# Triggy.net
KiCad netlist of a schematic drawn in EAGLE
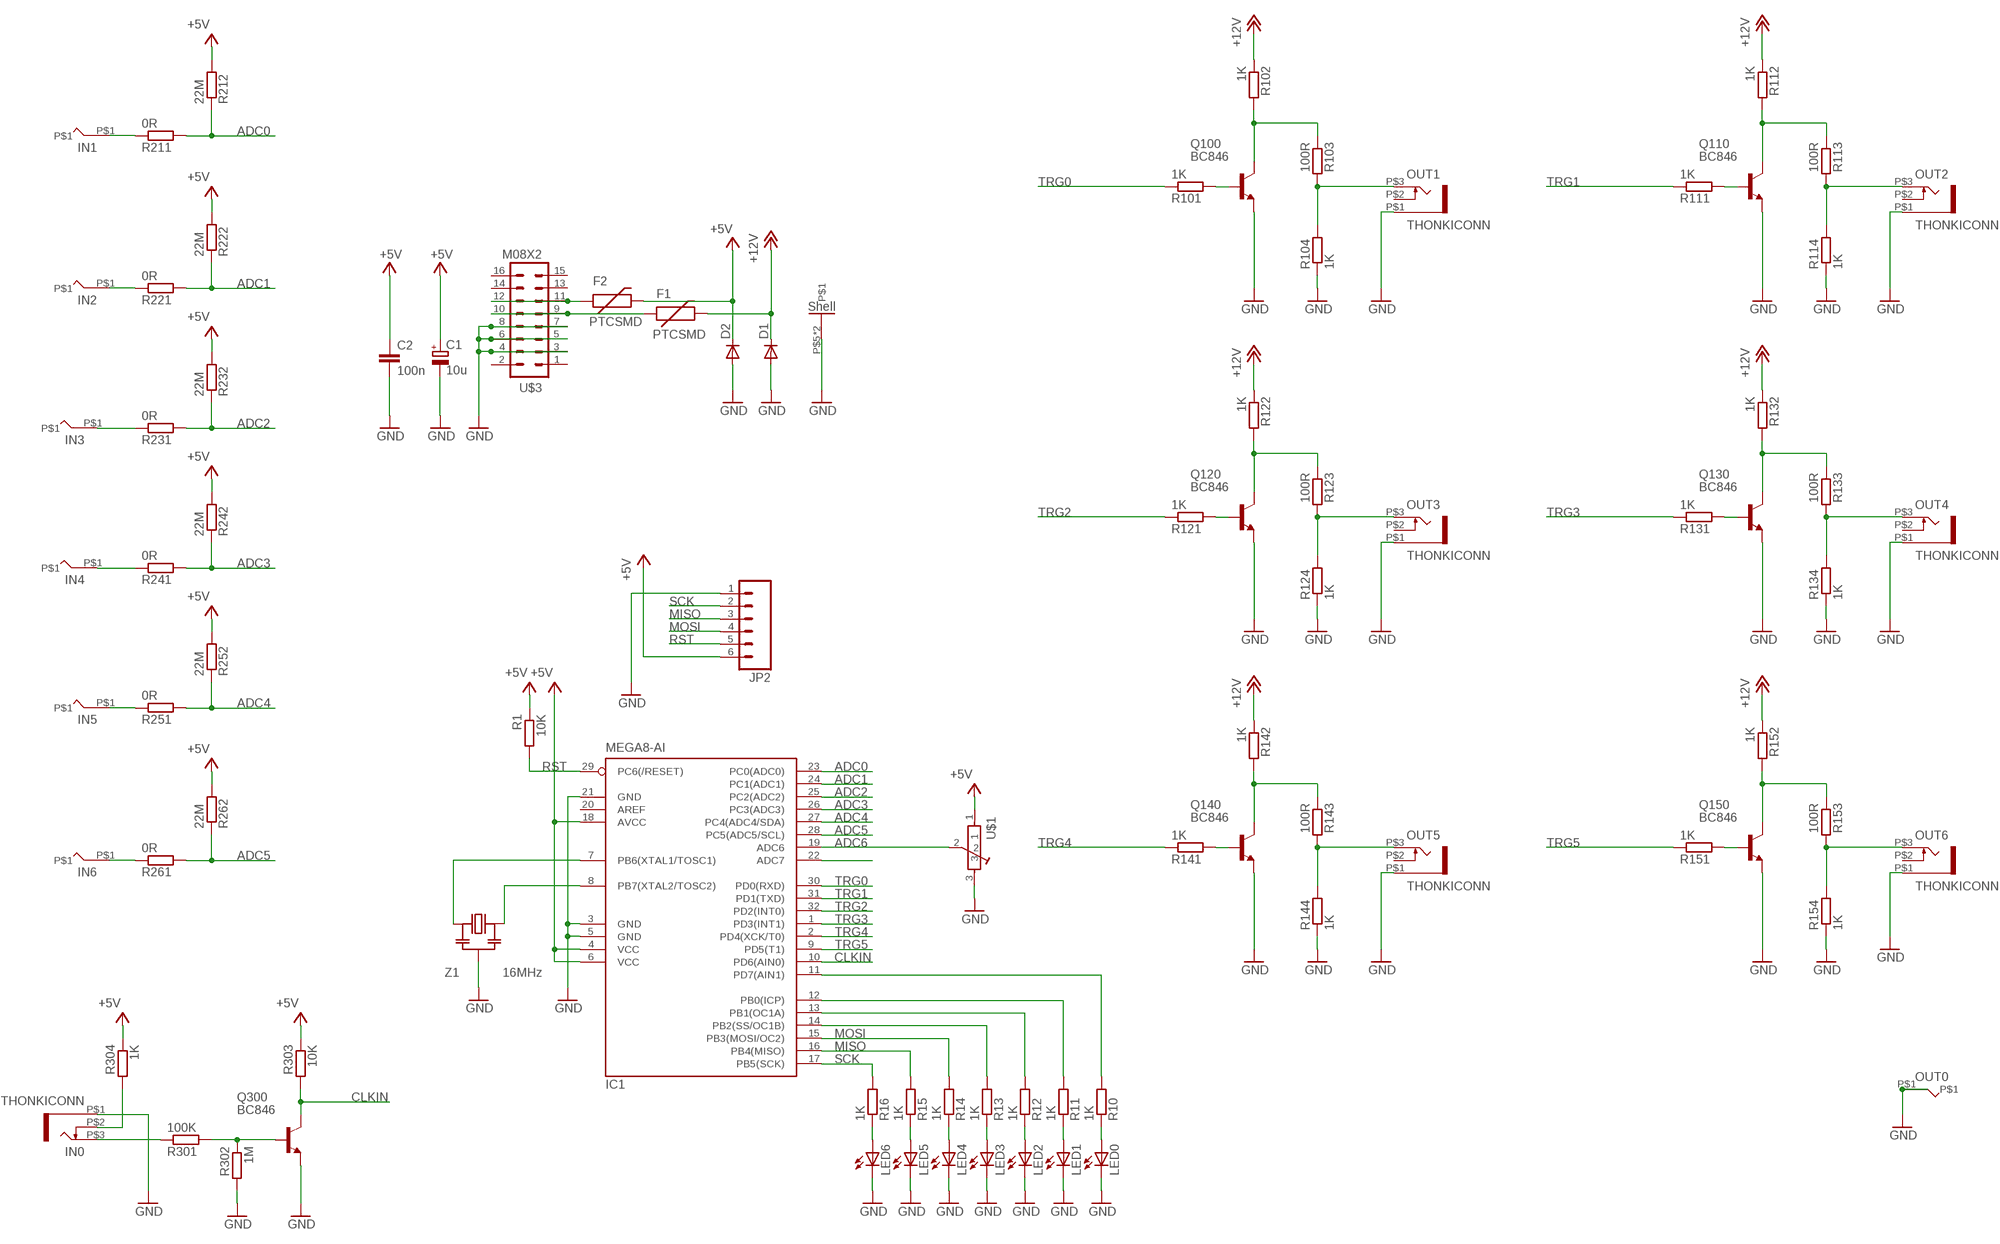
[diagram p0: schematic, sheet 1]

(export (version "E")
  (design (tool "Eeschema 10.0.6"))
  (components
    (comp (ref "C1")
      (value "10u")
      (footprint "eagle-import:E2,5-6")
      (libsource (lib "eagle-import") (part "CPOL-EUE2.5-6"))
    )
    (comp (ref "C2")
      (value "100n")
      (footprint "eagle-import:C0603")
      (libsource (lib "eagle-import") (part "C-EUC0603"))
    )
    (comp (ref "D1")
      (value "DIODESMA")
      (footprint "eagle-import:SMA-DIODE")
      (libsource (lib "eagle-import") (part "DIODESMA"))
    )
    (comp (ref "D2")
      (value "DIODESMA")
      (footprint "eagle-import:SMA-DIODE")
      (libsource (lib "eagle-import") (part "DIODESMA"))
    )
    (comp (ref "F1")
      (value "PTCSMD")
      (footprint "eagle-import:PTC-1206")
      (libsource (lib "eagle-import") (part "PTCSMD"))
    )
    (comp (ref "F2")
      (value "PTCSMD")
      (footprint "eagle-import:PTC-1206")
      (libsource (lib "eagle-import") (part "PTCSMD"))
    )
    (comp (ref "IC1")
      (value "MEGA8-AI")
      (footprint "eagle-import:TQFP32-08")
      (fields (field (name "MPN") "ATMEGA8-16AU"))
      (libsource (lib "eagle-import") (part "MEGA8-AI"))
    )
    (comp (ref "IN0")
      (value "THONKICONN")
      (footprint "eagle-import:THONKICONN")
      (libsource (lib "eagle-import") (part "THONKICONN"))
    )
    (comp (ref "IN1")
      (value "BANANAJACK")
      (footprint "eagle-import:BANANAJACK")
      (libsource (lib "eagle-import") (part "BANANAJACK"))
    )
    (comp (ref "IN2")
      (value "BANANAJACK")
      (footprint "eagle-import:BANANAJACK")
      (libsource (lib "eagle-import") (part "BANANAJACK"))
    )
    (comp (ref "IN3")
      (value "BANANAJACK")
      (footprint "eagle-import:BANANAJACK")
      (libsource (lib "eagle-import") (part "BANANAJACK"))
    )
    (comp (ref "IN4")
      (value "BANANAJACK")
      (footprint "eagle-import:BANANAJACK")
      (libsource (lib "eagle-import") (part "BANANAJACK"))
    )
    (comp (ref "IN5")
      (value "BANANAJACK")
      (footprint "eagle-import:BANANAJACK")
      (libsource (lib "eagle-import") (part "BANANAJACK"))
    )
    (comp (ref "IN6")
      (value "BANANAJACK")
      (footprint "eagle-import:BANANAJACK")
      (libsource (lib "eagle-import") (part "BANANAJACK"))
    )
    (comp (ref "JP2")
      (value "M06SIP")
      (footprint "eagle-import:1X06")
      (libsource (lib "eagle-import") (part "M06SIP"))
    )
    (comp (ref "LED0")
      (value "LED3MM")
      (footprint "eagle-import:LED3MM")
      (libsource (lib "eagle-import") (part "LED3MM"))
    )
    (comp (ref "LED1")
      (value "LED3MM")
      (footprint "eagle-import:LED3MM")
      (libsource (lib "eagle-import") (part "LED3MM"))
    )
    (comp (ref "LED2")
      (value "LED3MM")
      (footprint "eagle-import:LED3MM")
      (libsource (lib "eagle-import") (part "LED3MM"))
    )
    (comp (ref "LED3")
      (value "LED3MM")
      (footprint "eagle-import:LED3MM")
      (libsource (lib "eagle-import") (part "LED3MM"))
    )
    (comp (ref "LED4")
      (value "LED3MM")
      (footprint "eagle-import:LED3MM")
      (libsource (lib "eagle-import") (part "LED3MM"))
    )
    (comp (ref "LED5")
      (value "LED3MM")
      (footprint "eagle-import:LED3MM")
      (libsource (lib "eagle-import") (part "LED3MM"))
    )
    (comp (ref "LED6")
      (value "LED3MM")
      (footprint "eagle-import:LED3MM")
      (libsource (lib "eagle-import") (part "LED3MM"))
    )
    (comp (ref "OUT0")
      (value "BANANAJACK")
      (footprint "eagle-import:BANANAJACK")
      (libsource (lib "eagle-import") (part "BANANAJACK"))
    )
    (comp (ref "OUT1")
      (value "THONKICONN")
      (footprint "eagle-import:THONKICONN")
      (libsource (lib "eagle-import") (part "THONKICONN"))
    )
    (comp (ref "OUT2")
      (value "THONKICONN")
      (footprint "eagle-import:THONKICONN")
      (libsource (lib "eagle-import") (part "THONKICONN"))
    )
    (comp (ref "OUT3")
      (value "THONKICONN")
      (footprint "eagle-import:THONKICONN")
      (libsource (lib "eagle-import") (part "THONKICONN"))
    )
    (comp (ref "OUT4")
      (value "THONKICONN")
      (footprint "eagle-import:THONKICONN")
      (libsource (lib "eagle-import") (part "THONKICONN"))
    )
    (comp (ref "OUT5")
      (value "THONKICONN")
      (footprint "eagle-import:THONKICONN")
      (libsource (lib "eagle-import") (part "THONKICONN"))
    )
    (comp (ref "OUT6")
      (value "THONKICONN")
      (footprint "eagle-import:THONKICONN")
      (libsource (lib "eagle-import") (part "THONKICONN"))
    )
    (comp (ref "Q100")
      (value "BC846")
      (footprint "eagle-import:SOT23")
      (libsource (lib "eagle-import") (part "BC846"))
    )
    (comp (ref "Q110")
      (value "BC846")
      (footprint "eagle-import:SOT23")
      (libsource (lib "eagle-import") (part "BC846"))
    )
    (comp (ref "Q120")
      (value "BC846")
      (footprint "eagle-import:SOT23")
      (libsource (lib "eagle-import") (part "BC846"))
    )
    (comp (ref "Q130")
      (value "BC846")
      (footprint "eagle-import:SOT23")
      (libsource (lib "eagle-import") (part "BC846"))
    )
    (comp (ref "Q140")
      (value "BC846")
      (footprint "eagle-import:SOT23")
      (libsource (lib "eagle-import") (part "BC846"))
    )
    (comp (ref "Q150")
      (value "BC846")
      (footprint "eagle-import:SOT23")
      (libsource (lib "eagle-import") (part "BC846"))
    )
    (comp (ref "Q300")
      (value "BC846")
      (footprint "eagle-import:SOT23")
      (libsource (lib "eagle-import") (part "BC846"))
    )
    (comp (ref "R1")
      (value "10K")
      (footprint "eagle-import:0603")
      (libsource (lib "eagle-import") (part "R-EU_0603"))
    )
    (comp (ref "R10")
      (value "1K")
      (footprint "eagle-import:0603")
      (libsource (lib "eagle-import") (part "R-EU_0603"))
    )
    (comp (ref "R11")
      (value "1K")
      (footprint "eagle-import:0603")
      (libsource (lib "eagle-import") (part "R-EU_0603"))
    )
    (comp (ref "R12")
      (value "1K")
      (footprint "eagle-import:0603")
      (libsource (lib "eagle-import") (part "R-EU_0603"))
    )
    (comp (ref "R13")
      (value "1K")
      (footprint "eagle-import:0603")
      (libsource (lib "eagle-import") (part "R-EU_0603"))
    )
    (comp (ref "R14")
      (value "1K")
      (footprint "eagle-import:0603")
      (libsource (lib "eagle-import") (part "R-EU_0603"))
    )
    (comp (ref "R15")
      (value "1K")
      (footprint "eagle-import:0603")
      (libsource (lib "eagle-import") (part "R-EU_0603"))
    )
    (comp (ref "R16")
      (value "1K")
      (footprint "eagle-import:0603")
      (libsource (lib "eagle-import") (part "R-EU_0603"))
    )
    (comp (ref "R101")
      (value "1K")
      (footprint "eagle-import:0603")
      (libsource (lib "eagle-import") (part "R-EU_0603"))
    )
    (comp (ref "R102")
      (value "1K")
      (footprint "eagle-import:0603")
      (libsource (lib "eagle-import") (part "R-EU_0603"))
    )
    (comp (ref "R103")
      (value "100R")
      (footprint "eagle-import:0603")
      (libsource (lib "eagle-import") (part "R-EU_0603"))
    )
    (comp (ref "R104")
      (value "1K")
      (footprint "eagle-import:0603")
      (libsource (lib "eagle-import") (part "R-EU_0603"))
    )
    (comp (ref "R111")
      (value "1K")
      (footprint "eagle-import:0603")
      (libsource (lib "eagle-import") (part "R-EU_0603"))
    )
    (comp (ref "R112")
      (value "1K")
      (footprint "eagle-import:0603")
      (libsource (lib "eagle-import") (part "R-EU_0603"))
    )
    (comp (ref "R113")
      (value "100R")
      (footprint "eagle-import:0603")
      (libsource (lib "eagle-import") (part "R-EU_0603"))
    )
    (comp (ref "R114")
      (value "1K")
      (footprint "eagle-import:0603")
      (libsource (lib "eagle-import") (part "R-EU_0603"))
    )
    (comp (ref "R121")
      (value "1K")
      (footprint "eagle-import:0603")
      (libsource (lib "eagle-import") (part "R-EU_0603"))
    )
    (comp (ref "R122")
      (value "1K")
      (footprint "eagle-import:0603")
      (libsource (lib "eagle-import") (part "R-EU_0603"))
    )
    (comp (ref "R123")
      (value "100R")
      (footprint "eagle-import:0603")
      (libsource (lib "eagle-import") (part "R-EU_0603"))
    )
    (comp (ref "R124")
      (value "1K")
      (footprint "eagle-import:0603")
      (libsource (lib "eagle-import") (part "R-EU_0603"))
    )
    (comp (ref "R131")
      (value "1K")
      (footprint "eagle-import:0603")
      (libsource (lib "eagle-import") (part "R-EU_0603"))
    )
    (comp (ref "R132")
      (value "1K")
      (footprint "eagle-import:0603")
      (libsource (lib "eagle-import") (part "R-EU_0603"))
    )
    (comp (ref "R133")
      (value "100R")
      (footprint "eagle-import:0603")
      (libsource (lib "eagle-import") (part "R-EU_0603"))
    )
    (comp (ref "R134")
      (value "1K")
      (footprint "eagle-import:0603")
      (libsource (lib "eagle-import") (part "R-EU_0603"))
    )
    (comp (ref "R141")
      (value "1K")
      (footprint "eagle-import:0603")
      (libsource (lib "eagle-import") (part "R-EU_0603"))
    )
    (comp (ref "R142")
      (value "1K")
      (footprint "eagle-import:0603")
      (libsource (lib "eagle-import") (part "R-EU_0603"))
    )
    (comp (ref "R143")
      (value "100R")
      (footprint "eagle-import:0603")
      (libsource (lib "eagle-import") (part "R-EU_0603"))
    )
    (comp (ref "R144")
      (value "1K")
      (footprint "eagle-import:0603")
      (libsource (lib "eagle-import") (part "R-EU_0603"))
    )
    (comp (ref "R151")
      (value "1K")
      (footprint "eagle-import:0603")
      (libsource (lib "eagle-import") (part "R-EU_0603"))
    )
    (comp (ref "R152")
      (value "1K")
      (footprint "eagle-import:0603")
      (libsource (lib "eagle-import") (part "R-EU_0603"))
    )
    (comp (ref "R153")
      (value "100R")
      (footprint "eagle-import:0603")
      (libsource (lib "eagle-import") (part "R-EU_0603"))
    )
    (comp (ref "R154")
      (value "1K")
      (footprint "eagle-import:0603")
      (libsource (lib "eagle-import") (part "R-EU_0603"))
    )
    (comp (ref "R211")
      (value "0R")
      (footprint "eagle-import:0603")
      (libsource (lib "eagle-import") (part "R-EU_0603"))
    )
    (comp (ref "R212")
      (value "22M")
      (footprint "eagle-import:0603")
      (libsource (lib "eagle-import") (part "R-EU_0603"))
    )
    (comp (ref "R221")
      (value "0R")
      (footprint "eagle-import:0603")
      (libsource (lib "eagle-import") (part "R-EU_0603"))
    )
    (comp (ref "R222")
      (value "22M")
      (footprint "eagle-import:0603")
      (libsource (lib "eagle-import") (part "R-EU_0603"))
    )
    (comp (ref "R231")
      (value "0R")
      (footprint "eagle-import:0603")
      (libsource (lib "eagle-import") (part "R-EU_0603"))
    )
    (comp (ref "R232")
      (value "22M")
      (footprint "eagle-import:0603")
      (libsource (lib "eagle-import") (part "R-EU_0603"))
    )
    (comp (ref "R241")
      (value "0R")
      (footprint "eagle-import:0603")
      (libsource (lib "eagle-import") (part "R-EU_0603"))
    )
    (comp (ref "R242")
      (value "22M")
      (footprint "eagle-import:0603")
      (libsource (lib "eagle-import") (part "R-EU_0603"))
    )
    (comp (ref "R251")
      (value "0R")
      (footprint "eagle-import:0603")
      (libsource (lib "eagle-import") (part "R-EU_0603"))
    )
    (comp (ref "R252")
      (value "22M")
      (footprint "eagle-import:0603")
      (libsource (lib "eagle-import") (part "R-EU_0603"))
    )
    (comp (ref "R261")
      (value "0R")
      (footprint "eagle-import:0603")
      (libsource (lib "eagle-import") (part "R-EU_0603"))
    )
    (comp (ref "R262")
      (value "22M")
      (footprint "eagle-import:0603")
      (libsource (lib "eagle-import") (part "R-EU_0603"))
    )
    (comp (ref "R301")
      (value "100K")
      (footprint "eagle-import:0603")
      (libsource (lib "eagle-import") (part "R-EU_0603"))
    )
    (comp (ref "R302")
      (value "1M")
      (footprint "eagle-import:0603")
      (libsource (lib "eagle-import") (part "R-EU_0603"))
    )
    (comp (ref "R303")
      (value "10K")
      (footprint "eagle-import:0603")
      (libsource (lib "eagle-import") (part "R-EU_0603"))
    )
    (comp (ref "R304")
      (value "1K")
      (footprint "eagle-import:0603")
      (libsource (lib "eagle-import") (part "R-EU_0603"))
    )
    (comp (ref "U$1")
      (value "POT-ALPS-RK09L1140")
      (footprint "eagle-import:POT-ALPS-RK09L1140")
      (libsource (lib "eagle-import") (part "POT-ALPS-RK09L1140"))
    )
    (comp (ref "U$3")
      (value "M08X2")
      (footprint "eagle-import:2X8")
      (libsource (lib "eagle-import") (part "M08X2"))
    )
    (comp (ref "Z1")
      (value "16MHz")
      (footprint "eagle-import:CSTCE_G_A")
      (libsource (lib "eagle-import") (part "CERAMIC_RESONATOR"))
    )
  )
  (nets
    (net (code "1") (name "+5V") (class "Default")
      (node (ref "C1") (pin "+") (pinfunction "+_+") (pintype "passive"))
      (node (ref "C2") (pin "1") (pinfunction "1_1") (pintype "passive"))
      (node (ref "D2") (pin "C") (pinfunction "C_C") (pintype "passive"))
      (node (ref "F2") (pin "2") (pinfunction "2_2") (pintype "bidirectional"))
      (node (ref "IC1") (pin "18") (pinfunction "AVCC_18") (pintype "power_in"))
      (node (ref "IC1") (pin "4") (pinfunction "VCC_4") (pintype "power_in"))
      (node (ref "IC1") (pin "6") (pinfunction "VCC_6") (pintype "power_in"))
      (node (ref "JP2") (pin "6") (pinfunction "6_6") (pintype "passive"))
      (node (ref "R1") (pin "1") (pinfunction "1_1") (pintype "passive"))
      (node (ref "R212") (pin "2") (pinfunction "2_2") (pintype "passive"))
      (node (ref "R222") (pin "2") (pinfunction "2_2") (pintype "passive"))
      (node (ref "R232") (pin "2") (pinfunction "2_2") (pintype "passive"))
      (node (ref "R242") (pin "2") (pinfunction "2_2") (pintype "passive"))
      (node (ref "R252") (pin "2") (pinfunction "2_2") (pintype "passive"))
      (node (ref "R262") (pin "2") (pinfunction "2_2") (pintype "passive"))
      (node (ref "R303") (pin "1") (pinfunction "1_1") (pintype "passive"))
      (node (ref "R304") (pin "1") (pinfunction "1_1") (pintype "passive"))
      (node (ref "U$1") (pin "1") (pinfunction "1_1") (pintype "bidirectional"))
    )
    (net (code "2") (name "+12V") (class "Default")
      (node (ref "D1") (pin "C") (pinfunction "C_C") (pintype "passive"))
      (node (ref "F1") (pin "2") (pinfunction "2_2") (pintype "bidirectional"))
      (node (ref "R102") (pin "1") (pinfunction "1_1") (pintype "passive"))
      (node (ref "R112") (pin "1") (pinfunction "1_1") (pintype "passive"))
      (node (ref "R122") (pin "1") (pinfunction "1_1") (pintype "passive"))
      (node (ref "R132") (pin "1") (pinfunction "1_1") (pintype "passive"))
      (node (ref "R142") (pin "1") (pinfunction "1_1") (pintype "passive"))
      (node (ref "R152") (pin "1") (pinfunction "1_1") (pintype "passive"))
    )
    (net (code "3") (name "/ADC0") (class "Default")
      (node (ref "IC1") (pin "23") (pinfunction "PC0(ADC0)_23") (pintype "bidirectional"))
      (node (ref "R211") (pin "2") (pinfunction "2_2") (pintype "passive"))
      (node (ref "R212") (pin "1") (pinfunction "1_1") (pintype "passive"))
    )
    (net (code "4") (name "/ADC1") (class "Default")
      (node (ref "IC1") (pin "24") (pinfunction "PC1(ADC1)_24") (pintype "bidirectional"))
      (node (ref "R221") (pin "2") (pinfunction "2_2") (pintype "passive"))
      (node (ref "R222") (pin "1") (pinfunction "1_1") (pintype "passive"))
    )
    (net (code "5") (name "/ADC2") (class "Default")
      (node (ref "IC1") (pin "25") (pinfunction "PC2(ADC2)_25") (pintype "bidirectional"))
      (node (ref "R231") (pin "2") (pinfunction "2_2") (pintype "passive"))
      (node (ref "R232") (pin "1") (pinfunction "1_1") (pintype "passive"))
    )
    (net (code "6") (name "/ADC3") (class "Default")
      (node (ref "IC1") (pin "26") (pinfunction "PC3(ADC3)_26") (pintype "bidirectional"))
      (node (ref "R241") (pin "2") (pinfunction "2_2") (pintype "passive"))
      (node (ref "R242") (pin "1") (pinfunction "1_1") (pintype "passive"))
    )
    (net (code "7") (name "/ADC4") (class "Default")
      (node (ref "IC1") (pin "27") (pinfunction "PC4(ADC4/SDA)_27") (pintype "bidirectional"))
      (node (ref "R251") (pin "2") (pinfunction "2_2") (pintype "passive"))
      (node (ref "R252") (pin "1") (pinfunction "1_1") (pintype "passive"))
    )
    (net (code "8") (name "/ADC5") (class "Default")
      (node (ref "IC1") (pin "28") (pinfunction "PC5(ADC5/SCL)_28") (pintype "bidirectional"))
      (node (ref "R261") (pin "2") (pinfunction "2_2") (pintype "passive"))
      (node (ref "R262") (pin "1") (pinfunction "1_1") (pintype "passive"))
    )
    (net (code "9") (name "/ADC6") (class "Default")
      (node (ref "IC1") (pin "19") (pinfunction "ADC6_19") (pintype "bidirectional"))
      (node (ref "U$1") (pin "2") (pinfunction "2_2") (pintype "bidirectional"))
    )
    (net (code "10") (name "/CLKIN") (class "Default")
      (node (ref "IC1") (pin "10") (pinfunction "PD6(AIN0)_10") (pintype "bidirectional"))
      (node (ref "Q300") (pin "3") (pinfunction "C_3") (pintype "passive"))
      (node (ref "R303") (pin "2") (pinfunction "2_2") (pintype "passive"))
    )
    (net (code "11") (name "/MISO") (class "Default")
      (node (ref "IC1") (pin "16") (pinfunction "PB4(MISO)_16") (pintype "bidirectional"))
      (node (ref "JP2") (pin "3") (pinfunction "3_3") (pintype "passive"))
      (node (ref "R15") (pin "2") (pinfunction "2_2") (pintype "passive"))
    )
    (net (code "12") (name "/MOSI") (class "Default")
      (node (ref "IC1") (pin "15") (pinfunction "PB3(MOSI/OC2)_15") (pintype "bidirectional"))
      (node (ref "JP2") (pin "4") (pinfunction "4_4") (pintype "passive"))
      (node (ref "R14") (pin "2") (pinfunction "2_2") (pintype "passive"))
    )
    (net (code "13") (name "/RST") (class "Default")
      (node (ref "IC1") (pin "29") (pinfunction "PC6(/RESET)_29") (pintype "bidirectional"))
      (node (ref "JP2") (pin "5") (pinfunction "5_5") (pintype "passive"))
      (node (ref "R1") (pin "2") (pinfunction "2_2") (pintype "passive"))
    )
    (net (code "14") (name "/SCK") (class "Default")
      (node (ref "IC1") (pin "17") (pinfunction "PB5(SCK)_17") (pintype "bidirectional"))
      (node (ref "JP2") (pin "2") (pinfunction "2_2") (pintype "passive"))
      (node (ref "R16") (pin "2") (pinfunction "2_2") (pintype "passive"))
    )
    (net (code "15") (name "/TRG0") (class "Default")
      (node (ref "IC1") (pin "30") (pinfunction "PD0(RXD)_30") (pintype "bidirectional"))
      (node (ref "R101") (pin "1") (pinfunction "1_1") (pintype "passive"))
    )
    (net (code "16") (name "/TRG1") (class "Default")
      (node (ref "IC1") (pin "31") (pinfunction "PD1(TXD)_31") (pintype "bidirectional"))
      (node (ref "R111") (pin "1") (pinfunction "1_1") (pintype "passive"))
    )
    (net (code "17") (name "/TRG2") (class "Default")
      (node (ref "IC1") (pin "32") (pinfunction "PD2(INT0)_32") (pintype "bidirectional"))
      (node (ref "R121") (pin "1") (pinfunction "1_1") (pintype "passive"))
    )
    (net (code "18") (name "/TRG3") (class "Default")
      (node (ref "IC1") (pin "1") (pinfunction "PD3(INT1)_1") (pintype "bidirectional"))
      (node (ref "R131") (pin "1") (pinfunction "1_1") (pintype "passive"))
    )
    (net (code "19") (name "/TRG4") (class "Default")
      (node (ref "IC1") (pin "2") (pinfunction "PD4(XCK/T0)_2") (pintype "bidirectional"))
      (node (ref "R141") (pin "1") (pinfunction "1_1") (pintype "passive"))
    )
    (net (code "20") (name "/TRG5") (class "Default")
      (node (ref "IC1") (pin "9") (pinfunction "PD5(T1)_9") (pintype "bidirectional"))
      (node (ref "R151") (pin "1") (pinfunction "1_1") (pintype "passive"))
    )
    (net (code "21") (name "GND") (class "Default")
      (node (ref "C1") (pin "-") (pinfunction "-_-") (pintype "passive"))
      (node (ref "C2") (pin "2") (pinfunction "2_2") (pintype "passive"))
      (node (ref "D1") (pin "A") (pinfunction "A_A") (pintype "passive"))
      (node (ref "D2") (pin "A") (pinfunction "A_A") (pintype "passive"))
      (node (ref "IC1") (pin "21") (pinfunction "GND_21") (pintype "power_in"))
      (node (ref "IC1") (pin "3") (pinfunction "GND_3") (pintype "power_in"))
      (node (ref "IC1") (pin "5") (pinfunction "GND_5") (pintype "power_in"))
      (node (ref "IN0") (pin "P$1") (pinfunction "5_P$1") (pintype "passive"))
      (node (ref "JP2") (pin "1") (pinfunction "1_1") (pintype "passive"))
      (node (ref "LED0") (pin "K") (pinfunction "C_K") (pintype "passive"))
      (node (ref "LED1") (pin "K") (pinfunction "C_K") (pintype "passive"))
      (node (ref "LED2") (pin "K") (pinfunction "C_K") (pintype "passive"))
      (node (ref "LED3") (pin "K") (pinfunction "C_K") (pintype "passive"))
      (node (ref "LED4") (pin "K") (pinfunction "C_K") (pintype "passive"))
      (node (ref "LED5") (pin "K") (pinfunction "C_K") (pintype "passive"))
      (node (ref "LED6") (pin "K") (pinfunction "C_K") (pintype "passive"))
      (node (ref "OUT0") (pin "P$1") (pinfunction "P$1_P$1") (pintype "bidirectional"))
      (node (ref "OUT1") (pin "P$1") (pinfunction "5_P$1") (pintype "passive"))
      (node (ref "OUT2") (pin "P$1") (pinfunction "5_P$1") (pintype "passive"))
      (node (ref "OUT3") (pin "P$1") (pinfunction "5_P$1") (pintype "passive"))
      (node (ref "OUT4") (pin "P$1") (pinfunction "5_P$1") (pintype "passive"))
      (node (ref "OUT5") (pin "P$1") (pinfunction "5_P$1") (pintype "passive"))
      (node (ref "OUT6") (pin "P$1") (pinfunction "5_P$1") (pintype "passive"))
      (node (ref "Q100") (pin "2") (pinfunction "E_2") (pintype "passive"))
      (node (ref "Q110") (pin "2") (pinfunction "E_2") (pintype "passive"))
      (node (ref "Q120") (pin "2") (pinfunction "E_2") (pintype "passive"))
      (node (ref "Q130") (pin "2") (pinfunction "E_2") (pintype "passive"))
      (node (ref "Q140") (pin "2") (pinfunction "E_2") (pintype "passive"))
      (node (ref "Q150") (pin "2") (pinfunction "E_2") (pintype "passive"))
      (node (ref "Q300") (pin "2") (pinfunction "E_2") (pintype "passive"))
      (node (ref "R104") (pin "1") (pinfunction "1_1") (pintype "passive"))
      (node (ref "R114") (pin "1") (pinfunction "1_1") (pintype "passive"))
      (node (ref "R124") (pin "1") (pinfunction "1_1") (pintype "passive"))
      (node (ref "R134") (pin "1") (pinfunction "1_1") (pintype "passive"))
      (node (ref "R144") (pin "1") (pinfunction "1_1") (pintype "passive"))
      (node (ref "R154") (pin "1") (pinfunction "1_1") (pintype "passive"))
      (node (ref "R302") (pin "2") (pinfunction "2_2") (pintype "passive"))
      (node (ref "U$1") (pin "3") (pinfunction "3_3") (pintype "bidirectional"))
      (node (ref "U$1") (pin "P$5") (pinfunction "P$1_P$5") (pintype "bidirectional"))
      (node (ref "U$1") (pin "P$6") (pinfunction "P$1_P$6") (pintype "bidirectional"))
      (node (ref "U$3") (pin "3") (pinfunction "3_3") (pintype "passive"))
      (node (ref "U$3") (pin "4") (pinfunction "4_4") (pintype "passive"))
      (node (ref "U$3") (pin "5") (pinfunction "5_5") (pintype "passive"))
      (node (ref "U$3") (pin "6") (pinfunction "6_6") (pintype "passive"))
      (node (ref "U$3") (pin "7") (pinfunction "7_7") (pintype "passive"))
      (node (ref "U$3") (pin "8") (pinfunction "8_8") (pintype "passive"))
      (node (ref "Z1") (pin "P$2") (pinfunction "GND_P$2") (pintype "bidirectional"))
    )
    (net (code "22") (name "Net-(F1-Pad1)") (class "Default")
      (node (ref "F1") (pin "1") (pinfunction "1_1") (pintype "bidirectional"))
      (node (ref "U$3") (pin "10") (pinfunction "10_10") (pintype "passive"))
      (node (ref "U$3") (pin "9") (pinfunction "9_9") (pintype "passive"))
    )
    (net (code "23") (name "Net-(F2-Pad1)") (class "Default")
      (node (ref "F2") (pin "1") (pinfunction "1_1") (pintype "bidirectional"))
      (node (ref "U$3") (pin "11") (pinfunction "11_11") (pintype "passive"))
      (node (ref "U$3") (pin "12") (pinfunction "12_12") (pintype "passive"))
    )
    (net (code "24") (name "Net-(IC1-PB0(ICP))") (class "Default")
      (node (ref "IC1") (pin "12") (pinfunction "PB0(ICP)_12") (pintype "bidirectional"))
      (node (ref "R11") (pin "2") (pinfunction "2_2") (pintype "passive"))
    )
    (net (code "25") (name "Net-(IC1-PB1(OC1A))") (class "Default")
      (node (ref "IC1") (pin "13") (pinfunction "PB1(OC1A)_13") (pintype "bidirectional"))
      (node (ref "R12") (pin "2") (pinfunction "2_2") (pintype "passive"))
    )
    (net (code "26") (name "Net-(IC1-PB2(SS{slash}OC1B))") (class "Default")
      (node (ref "IC1") (pin "14") (pinfunction "PB2(SS/OC1B)_14") (pintype "bidirectional"))
      (node (ref "R13") (pin "2") (pinfunction "2_2") (pintype "passive"))
    )
    (net (code "27") (name "Net-(IC1-PB6(XTAL1{slash}TOSC1))") (class "Default")
      (node (ref "IC1") (pin "7") (pinfunction "PB6(XTAL1/TOSC1)_7") (pintype "bidirectional"))
      (node (ref "Z1") (pin "P$1") (pinfunction "IN_P$1") (pintype "bidirectional"))
    )
    (net (code "28") (name "Net-(IC1-PB7(XTAL2{slash}TOSC2))") (class "Default")
      (node (ref "IC1") (pin "8") (pinfunction "PB7(XTAL2/TOSC2)_8") (pintype "bidirectional"))
      (node (ref "Z1") (pin "P$3") (pinfunction "OUT_P$3") (pintype "bidirectional"))
    )
    (net (code "29") (name "Net-(IC1-PD7(AIN1))") (class "Default")
      (node (ref "IC1") (pin "11") (pinfunction "PD7(AIN1)_11") (pintype "bidirectional"))
      (node (ref "R10") (pin "2") (pinfunction "2_2") (pintype "passive"))
    )
    (net (code "30") (name "Net-(IN0-3)") (class "Default")
      (node (ref "IN0") (pin "P$3") (pinfunction "3_P$3") (pintype "passive"))
      (node (ref "R301") (pin "1") (pinfunction "1_1") (pintype "passive"))
    )
    (net (code "31") (name "Net-(IN0-4)") (class "Default")
      (node (ref "IN0") (pin "P$2") (pinfunction "4_P$2") (pintype "passive"))
      (node (ref "R304") (pin "2") (pinfunction "2_2") (pintype "passive"))
    )
    (net (code "32") (name "Net-(IN1-PadP$1)") (class "Default")
      (node (ref "IN1") (pin "P$1") (pinfunction "P$1_P$1") (pintype "bidirectional"))
      (node (ref "R211") (pin "1") (pinfunction "1_1") (pintype "passive"))
    )
    (net (code "33") (name "Net-(IN2-PadP$1)") (class "Default")
      (node (ref "IN2") (pin "P$1") (pinfunction "P$1_P$1") (pintype "bidirectional"))
      (node (ref "R221") (pin "1") (pinfunction "1_1") (pintype "passive"))
    )
    (net (code "34") (name "Net-(IN3-PadP$1)") (class "Default")
      (node (ref "IN3") (pin "P$1") (pinfunction "P$1_P$1") (pintype "bidirectional"))
      (node (ref "R231") (pin "1") (pinfunction "1_1") (pintype "passive"))
    )
    (net (code "35") (name "Net-(IN4-PadP$1)") (class "Default")
      (node (ref "IN4") (pin "P$1") (pinfunction "P$1_P$1") (pintype "bidirectional"))
      (node (ref "R241") (pin "1") (pinfunction "1_1") (pintype "passive"))
    )
    (net (code "36") (name "Net-(IN5-PadP$1)") (class "Default")
      (node (ref "IN5") (pin "P$1") (pinfunction "P$1_P$1") (pintype "bidirectional"))
      (node (ref "R251") (pin "1") (pinfunction "1_1") (pintype "passive"))
    )
    (net (code "37") (name "Net-(IN6-PadP$1)") (class "Default")
      (node (ref "IN6") (pin "P$1") (pinfunction "P$1_P$1") (pintype "bidirectional"))
      (node (ref "R261") (pin "1") (pinfunction "1_1") (pintype "passive"))
    )
    (net (code "38") (name "Net-(LED0-PadA)") (class "Default")
      (node (ref "LED0") (pin "A") (pinfunction "A_A") (pintype "passive"))
      (node (ref "R10") (pin "1") (pinfunction "1_1") (pintype "passive"))
    )
    (net (code "39") (name "Net-(LED1-PadA)") (class "Default")
      (node (ref "LED1") (pin "A") (pinfunction "A_A") (pintype "passive"))
      (node (ref "R11") (pin "1") (pinfunction "1_1") (pintype "passive"))
    )
    (net (code "40") (name "Net-(LED2-PadA)") (class "Default")
      (node (ref "LED2") (pin "A") (pinfunction "A_A") (pintype "passive"))
      (node (ref "R12") (pin "1") (pinfunction "1_1") (pintype "passive"))
    )
    (net (code "41") (name "Net-(LED3-PadA)") (class "Default")
      (node (ref "LED3") (pin "A") (pinfunction "A_A") (pintype "passive"))
      (node (ref "R13") (pin "1") (pinfunction "1_1") (pintype "passive"))
    )
    (net (code "42") (name "Net-(LED4-PadA)") (class "Default")
      (node (ref "LED4") (pin "A") (pinfunction "A_A") (pintype "passive"))
      (node (ref "R14") (pin "1") (pinfunction "1_1") (pintype "passive"))
    )
    (net (code "43") (name "Net-(LED5-PadA)") (class "Default")
      (node (ref "LED5") (pin "A") (pinfunction "A_A") (pintype "passive"))
      (node (ref "R15") (pin "1") (pinfunction "1_1") (pintype "passive"))
    )
    (net (code "44") (name "Net-(LED6-PadA)") (class "Default")
      (node (ref "LED6") (pin "A") (pinfunction "A_A") (pintype "passive"))
      (node (ref "R16") (pin "1") (pinfunction "1_1") (pintype "passive"))
    )
    (net (code "45") (name "Net-(OUT1-3)") (class "Default")
      (node (ref "OUT1") (pin "P$3") (pinfunction "3_P$3") (pintype "passive"))
      (node (ref "R103") (pin "2") (pinfunction "2_2") (pintype "passive"))
      (node (ref "R104") (pin "2") (pinfunction "2_2") (pintype "passive"))
    )
    (net (code "46") (name "Net-(OUT2-3)") (class "Default")
      (node (ref "OUT2") (pin "P$3") (pinfunction "3_P$3") (pintype "passive"))
      (node (ref "R113") (pin "2") (pinfunction "2_2") (pintype "passive"))
      (node (ref "R114") (pin "2") (pinfunction "2_2") (pintype "passive"))
    )
    (net (code "47") (name "Net-(OUT3-3)") (class "Default")
      (node (ref "OUT3") (pin "P$3") (pinfunction "3_P$3") (pintype "passive"))
      (node (ref "R123") (pin "2") (pinfunction "2_2") (pintype "passive"))
      (node (ref "R124") (pin "2") (pinfunction "2_2") (pintype "passive"))
    )
    (net (code "48") (name "Net-(OUT4-3)") (class "Default")
      (node (ref "OUT4") (pin "P$3") (pinfunction "3_P$3") (pintype "passive"))
      (node (ref "R133") (pin "2") (pinfunction "2_2") (pintype "passive"))
      (node (ref "R134") (pin "2") (pinfunction "2_2") (pintype "passive"))
    )
    (net (code "49") (name "Net-(OUT5-3)") (class "Default")
      (node (ref "OUT5") (pin "P$3") (pinfunction "3_P$3") (pintype "passive"))
      (node (ref "R143") (pin "2") (pinfunction "2_2") (pintype "passive"))
      (node (ref "R144") (pin "2") (pinfunction "2_2") (pintype "passive"))
    )
    (net (code "50") (name "Net-(OUT6-3)") (class "Default")
      (node (ref "OUT6") (pin "P$3") (pinfunction "3_P$3") (pintype "passive"))
      (node (ref "R153") (pin "2") (pinfunction "2_2") (pintype "passive"))
      (node (ref "R154") (pin "2") (pinfunction "2_2") (pintype "passive"))
    )
    (net (code "51") (name "Net-(Q100-B)") (class "Default")
      (node (ref "Q100") (pin "1") (pinfunction "B_1") (pintype "passive"))
      (node (ref "R101") (pin "2") (pinfunction "2_2") (pintype "passive"))
    )
    (net (code "52") (name "Net-(Q100-C)") (class "Default")
      (node (ref "Q100") (pin "3") (pinfunction "C_3") (pintype "passive"))
      (node (ref "R102") (pin "2") (pinfunction "2_2") (pintype "passive"))
      (node (ref "R103") (pin "1") (pinfunction "1_1") (pintype "passive"))
    )
    (net (code "53") (name "Net-(Q110-B)") (class "Default")
      (node (ref "Q110") (pin "1") (pinfunction "B_1") (pintype "passive"))
      (node (ref "R111") (pin "2") (pinfunction "2_2") (pintype "passive"))
    )
    (net (code "54") (name "Net-(Q110-C)") (class "Default")
      (node (ref "Q110") (pin "3") (pinfunction "C_3") (pintype "passive"))
      (node (ref "R112") (pin "2") (pinfunction "2_2") (pintype "passive"))
      (node (ref "R113") (pin "1") (pinfunction "1_1") (pintype "passive"))
    )
    (net (code "55") (name "Net-(Q120-B)") (class "Default")
      (node (ref "Q120") (pin "1") (pinfunction "B_1") (pintype "passive"))
      (node (ref "R121") (pin "2") (pinfunction "2_2") (pintype "passive"))
    )
    (net (code "56") (name "Net-(Q120-C)") (class "Default")
      (node (ref "Q120") (pin "3") (pinfunction "C_3") (pintype "passive"))
      (node (ref "R122") (pin "2") (pinfunction "2_2") (pintype "passive"))
      (node (ref "R123") (pin "1") (pinfunction "1_1") (pintype "passive"))
    )
    (net (code "57") (name "Net-(Q130-B)") (class "Default")
      (node (ref "Q130") (pin "1") (pinfunction "B_1") (pintype "passive"))
      (node (ref "R131") (pin "2") (pinfunction "2_2") (pintype "passive"))
    )
    (net (code "58") (name "Net-(Q130-C)") (class "Default")
      (node (ref "Q130") (pin "3") (pinfunction "C_3") (pintype "passive"))
      (node (ref "R132") (pin "2") (pinfunction "2_2") (pintype "passive"))
      (node (ref "R133") (pin "1") (pinfunction "1_1") (pintype "passive"))
    )
    (net (code "59") (name "Net-(Q140-B)") (class "Default")
      (node (ref "Q140") (pin "1") (pinfunction "B_1") (pintype "passive"))
      (node (ref "R141") (pin "2") (pinfunction "2_2") (pintype "passive"))
    )
    (net (code "60") (name "Net-(Q140-C)") (class "Default")
      (node (ref "Q140") (pin "3") (pinfunction "C_3") (pintype "passive"))
      (node (ref "R142") (pin "2") (pinfunction "2_2") (pintype "passive"))
      (node (ref "R143") (pin "1") (pinfunction "1_1") (pintype "passive"))
    )
    (net (code "61") (name "Net-(Q150-B)") (class "Default")
      (node (ref "Q150") (pin "1") (pinfunction "B_1") (pintype "passive"))
      (node (ref "R151") (pin "2") (pinfunction "2_2") (pintype "passive"))
    )
    (net (code "62") (name "Net-(Q150-C)") (class "Default")
      (node (ref "Q150") (pin "3") (pinfunction "C_3") (pintype "passive"))
      (node (ref "R152") (pin "2") (pinfunction "2_2") (pintype "passive"))
      (node (ref "R153") (pin "1") (pinfunction "1_1") (pintype "passive"))
    )
    (net (code "63") (name "Net-(Q300-B)") (class "Default")
      (node (ref "Q300") (pin "1") (pinfunction "B_1") (pintype "passive"))
      (node (ref "R301") (pin "2") (pinfunction "2_2") (pintype "passive"))
      (node (ref "R302") (pin "1") (pinfunction "1_1") (pintype "passive"))
    )
    (net (code "64") (name "unconnected-(IC1-ADC7-Pad22)") (class "Default")
      (node (ref "IC1") (pin "22") (pinfunction "ADC7_22") (pintype "bidirectional"))
    )
    (net (code "65") (name "unconnected-(IC1-AREF-Pad20)") (class "Default")
      (node (ref "IC1") (pin "20") (pinfunction "AREF_20") (pintype "passive"))
    )
    (net (code "66") (name "unconnected-(OUT1-4-PadP$2)") (class "Default")
      (node (ref "OUT1") (pin "P$2") (pinfunction "4_P$2") (pintype "passive"))
    )
    (net (code "67") (name "unconnected-(OUT2-4-PadP$2)") (class "Default")
      (node (ref "OUT2") (pin "P$2") (pinfunction "4_P$2") (pintype "passive"))
    )
    (net (code "68") (name "unconnected-(OUT3-4-PadP$2)") (class "Default")
      (node (ref "OUT3") (pin "P$2") (pinfunction "4_P$2") (pintype "passive"))
    )
    (net (code "69") (name "unconnected-(OUT4-4-PadP$2)") (class "Default")
      (node (ref "OUT4") (pin "P$2") (pinfunction "4_P$2") (pintype "passive"))
    )
    (net (code "70") (name "unconnected-(OUT5-4-PadP$2)") (class "Default")
      (node (ref "OUT5") (pin "P$2") (pinfunction "4_P$2") (pintype "passive"))
    )
    (net (code "71") (name "unconnected-(OUT6-4-PadP$2)") (class "Default")
      (node (ref "OUT6") (pin "P$2") (pinfunction "4_P$2") (pintype "passive"))
    )
    (net (code "72") (name "unconnected-(U$3-Pad1)") (class "Default")
      (node (ref "U$3") (pin "1") (pinfunction "1_1") (pintype "passive"))
    )
    (net (code "73") (name "unconnected-(U$3-Pad2)") (class "Default")
      (node (ref "U$3") (pin "2") (pinfunction "2_2") (pintype "passive"))
    )
    (net (code "74") (name "unconnected-(U$3-Pad13)") (class "Default")
      (node (ref "U$3") (pin "13") (pinfunction "13_13") (pintype "passive"))
    )
    (net (code "75") (name "unconnected-(U$3-Pad14)") (class "Default")
      (node (ref "U$3") (pin "14") (pinfunction "14_14") (pintype "passive"))
    )
    (net (code "76") (name "unconnected-(U$3-Pad15)") (class "Default")
      (node (ref "U$3") (pin "15") (pinfunction "15_15") (pintype "passive"))
    )
    (net (code "77") (name "unconnected-(U$3-Pad16)") (class "Default")
      (node (ref "U$3") (pin "16") (pinfunction "16_16") (pintype "passive"))
    )
  )
)
